# Sheet2.net
KiCad netlist of a schematic drawn in Altium Designer
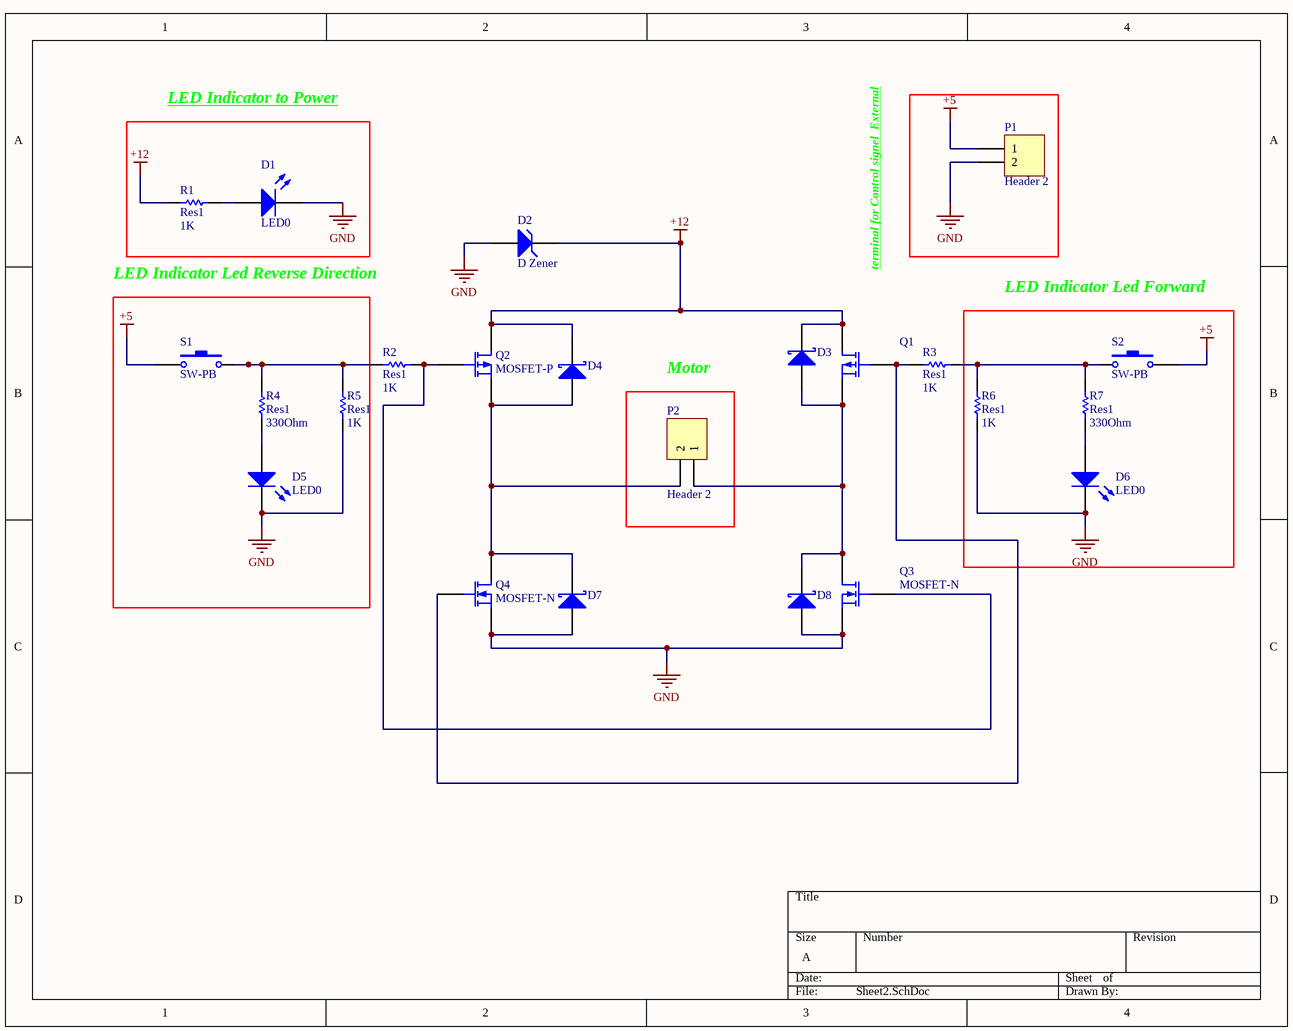
[diagram p0: Sheet2.SchDoc]

(export (version "E")
  (design (tool "Eeschema 10.0.6"))
  (components
    (comp (ref "D1")
      (value "LED0")
      (footprint "LED-0")
      (description "Typical INFRARED GaAs LED")
      (fields (field (name "PUBLISHER") "Altium Limited"))
      (libsource (lib "Miscellaneous Devices") (part "LED0"))
    )
    (comp (ref "D2")
      (value "D Zener")
      (footprint "DIODE-0.7")
      (description "Zener Diode")
      (fields (field (name "PUBLISHER") "Altium Limited"))
      (libsource (lib "Miscellaneous Devices") (part "D Zener"))
    )
    (comp (ref "D3")
      (value "Diode 10TQ045")
      (footprint "TO-220AC")
      (description "Schottky Rectifier")
      (fields (field (name "PUBLISHER") "Altium Limited"))
      (libsource (lib "Miscellaneous Devices") (part "Diode 10TQ045"))
    )
    (comp (ref "D4")
      (value "Diode 10TQ045")
      (footprint "TO-220AC")
      (description "Schottky Rectifier")
      (fields (field (name "PUBLISHER") "Altium Limited"))
      (libsource (lib "Miscellaneous Devices") (part "Diode 10TQ045"))
    )
    (comp (ref "D5")
      (value "LED0")
      (footprint "LED-0")
      (description "Typical INFRARED GaAs LED")
      (fields (field (name "PUBLISHER") "Altium Limited"))
      (libsource (lib "Miscellaneous Devices") (part "LED0"))
    )
    (comp (ref "D6")
      (value "LED0")
      (footprint "LED-0")
      (description "Typical INFRARED GaAs LED")
      (fields (field (name "PUBLISHER") "Altium Limited"))
      (libsource (lib "Miscellaneous Devices") (part "LED0"))
    )
    (comp (ref "D7")
      (value "Diode 10TQ045")
      (footprint "TO-220AC")
      (description "Schottky Rectifier")
      (fields (field (name "PUBLISHER") "Altium Limited"))
      (libsource (lib "Miscellaneous Devices") (part "Diode 10TQ045"))
    )
    (comp (ref "D8")
      (value "Diode 10TQ045")
      (footprint "TO-220AC")
      (description "Schottky Rectifier")
      (fields (field (name "PUBLISHER") "Altium Limited"))
      (libsource (lib "Miscellaneous Devices") (part "Diode 10TQ045"))
    )
    (comp (ref "P1")
      (value "Header 2")
      (footprint "HDR1X2")
      (description "Header, 2-Pin")
      (fields (field (name "PUBLISHER") "Altium Limited"))
      (libsource (lib "Miscellaneous Connectors") (part "Header 2"))
    )
    (comp (ref "P2")
      (value "Header 2")
      (footprint "HDR1X2")
      (description "Header, 2-Pin")
      (fields (field (name "PUBLISHER") "Altium Limited"))
      (libsource (lib "Miscellaneous Connectors") (part "Header 2"))
    )
    (comp (ref "Q1")
      (value "MOSFET-P")
      (footprint "E3")
      (description "P-Channel MOSFET")
      (fields (field (name "PUBLISHER") "Altium Limited"))
      (libsource (lib "Miscellaneous Devices") (part "MOSFET-P"))
    )
    (comp (ref "Q2")
      (value "MOSFET-P")
      (footprint "E3")
      (description "P-Channel MOSFET")
      (fields (field (name "PUBLISHER") "Altium Limited"))
      (libsource (lib "Miscellaneous Devices") (part "MOSFET-P"))
    )
    (comp (ref "Q3")
      (value "MOSFET-N")
      (footprint "E3")
      (description "N-Channel MOSFET")
      (fields (field (name "PUBLISHER") "Altium Limited"))
      (libsource (lib "Miscellaneous Devices") (part "MOSFET-N"))
    )
    (comp (ref "Q4")
      (value "MOSFET-N")
      (footprint "E3")
      (description "N-Channel MOSFET")
      (fields (field (name "PUBLISHER") "Altium Limited"))
      (libsource (lib "Miscellaneous Devices") (part "MOSFET-N"))
    )
    (comp (ref "R1")
      (value "Res1")
      (footprint "AXIAL-0.3")
      (description "Resistor")
      (fields (field (name "ALTIUM_VALUE") "1K") (field (name "PUBLISHER") "Altium Limited"))
      (libsource (lib "Miscellaneous Devices") (part "Res1"))
    )
    (comp (ref "R2")
      (value "Res1")
      (footprint "AXIAL-0.3")
      (description "Resistor")
      (fields (field (name "ALTIUM_VALUE") "1K") (field (name "PUBLISHER") "Altium Limited"))
      (libsource (lib "Miscellaneous Devices") (part "Res1"))
    )
    (comp (ref "R3")
      (value "Res1")
      (footprint "AXIAL-0.3")
      (description "Resistor")
      (fields (field (name "ALTIUM_VALUE") "1K") (field (name "PUBLISHER") "Altium Limited"))
      (libsource (lib "Miscellaneous Devices") (part "Res1"))
    )
    (comp (ref "R4")
      (value "Res1")
      (footprint "AXIAL-0.3")
      (description "Resistor")
      (fields (field (name "ALTIUM_VALUE") "330Ohm") (field (name "PUBLISHER") "Altium Limited"))
      (libsource (lib "Miscellaneous Devices") (part "Res1"))
    )
    (comp (ref "R5")
      (value "Res1")
      (footprint "AXIAL-0.3")
      (description "Resistor")
      (fields (field (name "ALTIUM_VALUE") "1K") (field (name "PUBLISHER") "Altium Limited"))
      (libsource (lib "Miscellaneous Devices") (part "Res1"))
    )
    (comp (ref "R6")
      (value "Res1")
      (footprint "AXIAL-0.3")
      (description "Resistor")
      (fields (field (name "ALTIUM_VALUE") "1K") (field (name "PUBLISHER") "Altium Limited"))
      (libsource (lib "Miscellaneous Devices") (part "Res1"))
    )
    (comp (ref "R7")
      (value "Res1")
      (footprint "AXIAL-0.3")
      (description "Resistor")
      (fields (field (name "ALTIUM_VALUE") "330Ohm") (field (name "PUBLISHER") "Altium Limited"))
      (libsource (lib "Miscellaneous Devices") (part "Res1"))
    )
    (comp (ref "S1")
      (value "SW-PB")
      (footprint "SPST-2")
      (description "Switch")
      (fields (field (name "PUBLISHER") "Altium Limited"))
      (libsource (lib "Miscellaneous Devices") (part "SW-PB"))
    )
    (comp (ref "S2")
      (value "SW-PB")
      (footprint "SPST-2")
      (description "Switch")
      (fields (field (name "PUBLISHER") "Altium Limited"))
      (libsource (lib "Miscellaneous Devices") (part "SW-PB"))
    )
  )
  (nets
    (net (code "1") (name "+5") (class "Default")
      (node (ref "P1") (pin "1") (pinfunction "1_1") (pintype "passive"))
      (node (ref "S1") (pin "1") (pinfunction "1_1") (pintype "passive"))
      (node (ref "S2") (pin "2") (pinfunction "2_2") (pintype "passive"))
    )
    (net (code "2") (name "+12") (class "Default")
      (node (ref "D2") (pin "2") (pinfunction "K_2") (pintype "passive"))
      (node (ref "D3") (pin "1") (pinfunction "K_1") (pintype "passive"))
      (node (ref "D4") (pin "1") (pinfunction "K_1") (pintype "passive"))
      (node (ref "Q1") (pin "1") (pinfunction "D_1") (pintype "passive"))
      (node (ref "Q2") (pin "1") (pinfunction "D_1") (pintype "passive"))
      (node (ref "R1") (pin "1") (pinfunction "1_1") (pintype "passive"))
    )
    (net (code "3") (name "GND") (class "Default")
      (node (ref "D1") (pin "2") (pinfunction "K_2") (pintype "passive"))
      (node (ref "D2") (pin "1") (pinfunction "A_1") (pintype "passive"))
      (node (ref "D5") (pin "2") (pinfunction "K_2") (pintype "passive"))
      (node (ref "D6") (pin "2") (pinfunction "K_2") (pintype "passive"))
      (node (ref "D7") (pin "3") (pinfunction "A_3") (pintype "passive"))
      (node (ref "D8") (pin "3") (pinfunction "A_3") (pintype "passive"))
      (node (ref "P1") (pin "2") (pinfunction "2_2") (pintype "passive"))
      (node (ref "Q3") (pin "3") (pinfunction "S_3") (pintype "passive"))
      (node (ref "Q4") (pin "3") (pinfunction "S_3") (pintype "passive"))
      (node (ref "R5") (pin "1") (pinfunction "1_1") (pintype "passive"))
      (node (ref "R6") (pin "1") (pinfunction "1_1") (pintype "passive"))
    )
    (net (code "4") (name "Net-(D1-A)") (class "Default")
      (node (ref "D1") (pin "1") (pinfunction "A_1") (pintype "passive"))
      (node (ref "R1") (pin "2") (pinfunction "2_2") (pintype "passive"))
    )
    (net (code "5") (name "Net-(D3-A)") (class "Default")
      (node (ref "D3") (pin "3") (pinfunction "A_3") (pintype "passive"))
      (node (ref "D8") (pin "1") (pinfunction "K_1") (pintype "passive"))
      (node (ref "P2") (pin "1") (pinfunction "1_1") (pintype "passive"))
      (node (ref "Q1") (pin "3") (pinfunction "S_3") (pintype "passive"))
      (node (ref "Q3") (pin "1") (pinfunction "D_1") (pintype "passive"))
    )
    (net (code "6") (name "Net-(D4-A)") (class "Default")
      (node (ref "D4") (pin "3") (pinfunction "A_3") (pintype "passive"))
      (node (ref "D7") (pin "1") (pinfunction "K_1") (pintype "passive"))
      (node (ref "P2") (pin "2") (pinfunction "2_2") (pintype "passive"))
      (node (ref "Q2") (pin "3") (pinfunction "S_3") (pintype "passive"))
      (node (ref "Q4") (pin "1") (pinfunction "D_1") (pintype "passive"))
    )
    (net (code "7") (name "Net-(D5-A)") (class "Default")
      (node (ref "D5") (pin "1") (pinfunction "A_1") (pintype "passive"))
      (node (ref "R4") (pin "1") (pinfunction "1_1") (pintype "passive"))
    )
    (net (code "8") (name "Net-(D6-A)") (class "Default")
      (node (ref "D6") (pin "1") (pinfunction "A_1") (pintype "passive"))
      (node (ref "R7") (pin "2") (pinfunction "2_2") (pintype "passive"))
    )
    (net (code "9") (name "Net-(Q1-G)") (class "Default")
      (node (ref "Q1") (pin "2") (pinfunction "G_2") (pintype "passive"))
      (node (ref "Q4") (pin "2") (pinfunction "G_2") (pintype "passive"))
      (node (ref "R3") (pin "1") (pinfunction "1_1") (pintype "passive"))
    )
    (net (code "10") (name "Net-(Q2-G)") (class "Default")
      (node (ref "Q2") (pin "2") (pinfunction "G_2") (pintype "passive"))
      (node (ref "Q3") (pin "2") (pinfunction "G_2") (pintype "passive"))
      (node (ref "R2") (pin "2") (pinfunction "2_2") (pintype "passive"))
    )
    (net (code "11") (name "Net-(R2-Pad1)") (class "Default")
      (node (ref "R2") (pin "1") (pinfunction "1_1") (pintype "passive"))
      (node (ref "R4") (pin "2") (pinfunction "2_2") (pintype "passive"))
      (node (ref "R5") (pin "2") (pinfunction "2_2") (pintype "passive"))
      (node (ref "S1") (pin "2") (pinfunction "2_2") (pintype "passive"))
    )
    (net (code "12") (name "Net-(R3-Pad2)") (class "Default")
      (node (ref "R3") (pin "2") (pinfunction "2_2") (pintype "passive"))
      (node (ref "R6") (pin "2") (pinfunction "2_2") (pintype "passive"))
      (node (ref "R7") (pin "1") (pinfunction "1_1") (pintype "passive"))
      (node (ref "S2") (pin "1") (pinfunction "1_1") (pintype "passive"))
    )
  )
)
